# Analog_Digital_Converter.net
KiCad netlist of a schematic drawn in Altium Designer
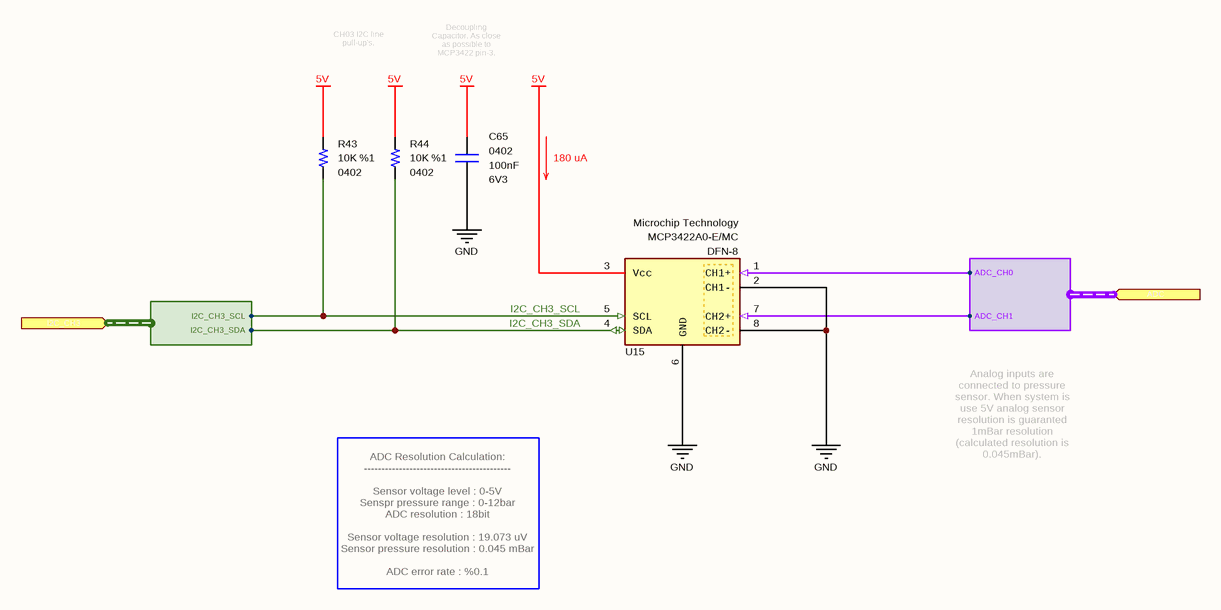
[diagram p0: Analog Digital Converter.SchDoc]

(export (version "E")
  (design (tool "Eeschema 10.0.6"))
  (components
    (comp (ref "C65")
      (value "100nF")
      (footprint "CAPACITOR_0402")
      (description "Capacitor - 100nF [0402-6V3] (Ceramic)")
      (fields
        (field (name "TOLERANCE") "%10")
        (field (name "CASE") "0402")
        (field (name "VOLTAGE") "6V3")
        (field (name "MANUFACTURER PART NUMBER") "04026D104KAT4A")
      )
      (libsource (lib "Ovoo_Library") (part "Capacitor - 100nF [0402-6V3]"))
    )
    (comp (ref "R43")
      (value "10K")
      (footprint "RESISTOR_0402")
      (description "Thick Film Resistors - SMD 1/16 W 10 Kohms 1%")
      (fields
        (field (name "TOLERANCE") "%1")
        (field (name "CASE") "0402")
        (field (name "MANUFACTURER PART NUMBER") "CRCW040210K0FKED")
        (field (name "MOUSER PART NUMBER") "71-CRCW0402-10K-E3")
      )
      (libsource (lib "Ovoo_Library") (part "Resistor - 10K"))
    )
    (comp (ref "R44")
      (value "10K")
      (footprint "RESISTOR_0402")
      (description "Thick Film Resistors - SMD 1/16 W 10 Kohms 1%")
      (fields
        (field (name "TOLERANCE") "%1")
        (field (name "CASE") "0402")
        (field (name "MANUFACTURER PART NUMBER") "CRCW040210K0FKED")
        (field (name "MOUSER PART NUMBER") "71-CRCW0402-10K-E3")
      )
      (libsource (lib "Ovoo_Library") (part "Resistor - 10K"))
    )
    (comp (ref "U15")
      (value "Analog to Digital Converters - ADC")
      (footprint "DFN-8")
      (description "Analog to Digital Converters - ADC 18B delta-sigma ADC dual Ch 4sps")
      (fields
        (field (name "CASE") "DFN-8")
        (field (name "MOUSER PART NUMBER") "579-MCP3422A0-E/MC")
        (field (name "MANUFACTURER PART NUMBER") "MCP3422A0-E/MC")
        (field (name "MANUFACTURER NAME") "Microchip Technology")
      )
      (libsource (lib "Ovoo_Library") (part "IC - MCP3422"))
    )
  )
  (nets
    (net (code "3") (name "/ADC_CH0") (class "Default")
      (node (ref "U15") (pin "1") (pinfunction "CH1+_1") (pintype "input"))
    )
    (net (code "4") (name "/ADC_CH1") (class "Default")
      (node (ref "U15") (pin "7") (pinfunction "CH2+_7") (pintype "input"))
    )
    (net (code "5") (name "/I2C_CH3_SCL") (class "Default")
      (node (ref "R43") (pin "1") (pinfunction "1_1") (pintype "passive"))
      (node (ref "U15") (pin "5") (pinfunction "SCL_5") (pintype "input"))
    )
    (net (code "6") (name "/I2C_CH3_SDA") (class "Default")
      (node (ref "R44") (pin "1") (pinfunction "1_1") (pintype "passive"))
      (node (ref "U15") (pin "4") (pinfunction "SDA_4") (pintype "bidirectional"))
    )
    (net (code "9") (name "5V") (class "Default")
      (node (ref "C65") (pin "2") (pinfunction "2_2") (pintype "passive"))
      (node (ref "R43") (pin "2") (pinfunction "2_2") (pintype "passive"))
      (node (ref "R44") (pin "2") (pinfunction "2_2") (pintype "passive"))
      (node (ref "U15") (pin "3") (pinfunction "Vcc_3") (pintype "power_in"))
    )
    (net (code "10") (name "GND") (class "Default")
      (node (ref "C65") (pin "1") (pinfunction "1_1") (pintype "passive"))
      (node (ref "U15") (pin "2") (pinfunction "CH1-_2") (pintype "passive"))
      (node (ref "U15") (pin "6") (pinfunction "GND_6") (pintype "power_in"))
      (node (ref "U15") (pin "8") (pinfunction "CH2-_8") (pintype "passive"))
    )
  )
)
